# TempControl_V2_0.net
KiCad netlist of a schematic drawn in EAGLE
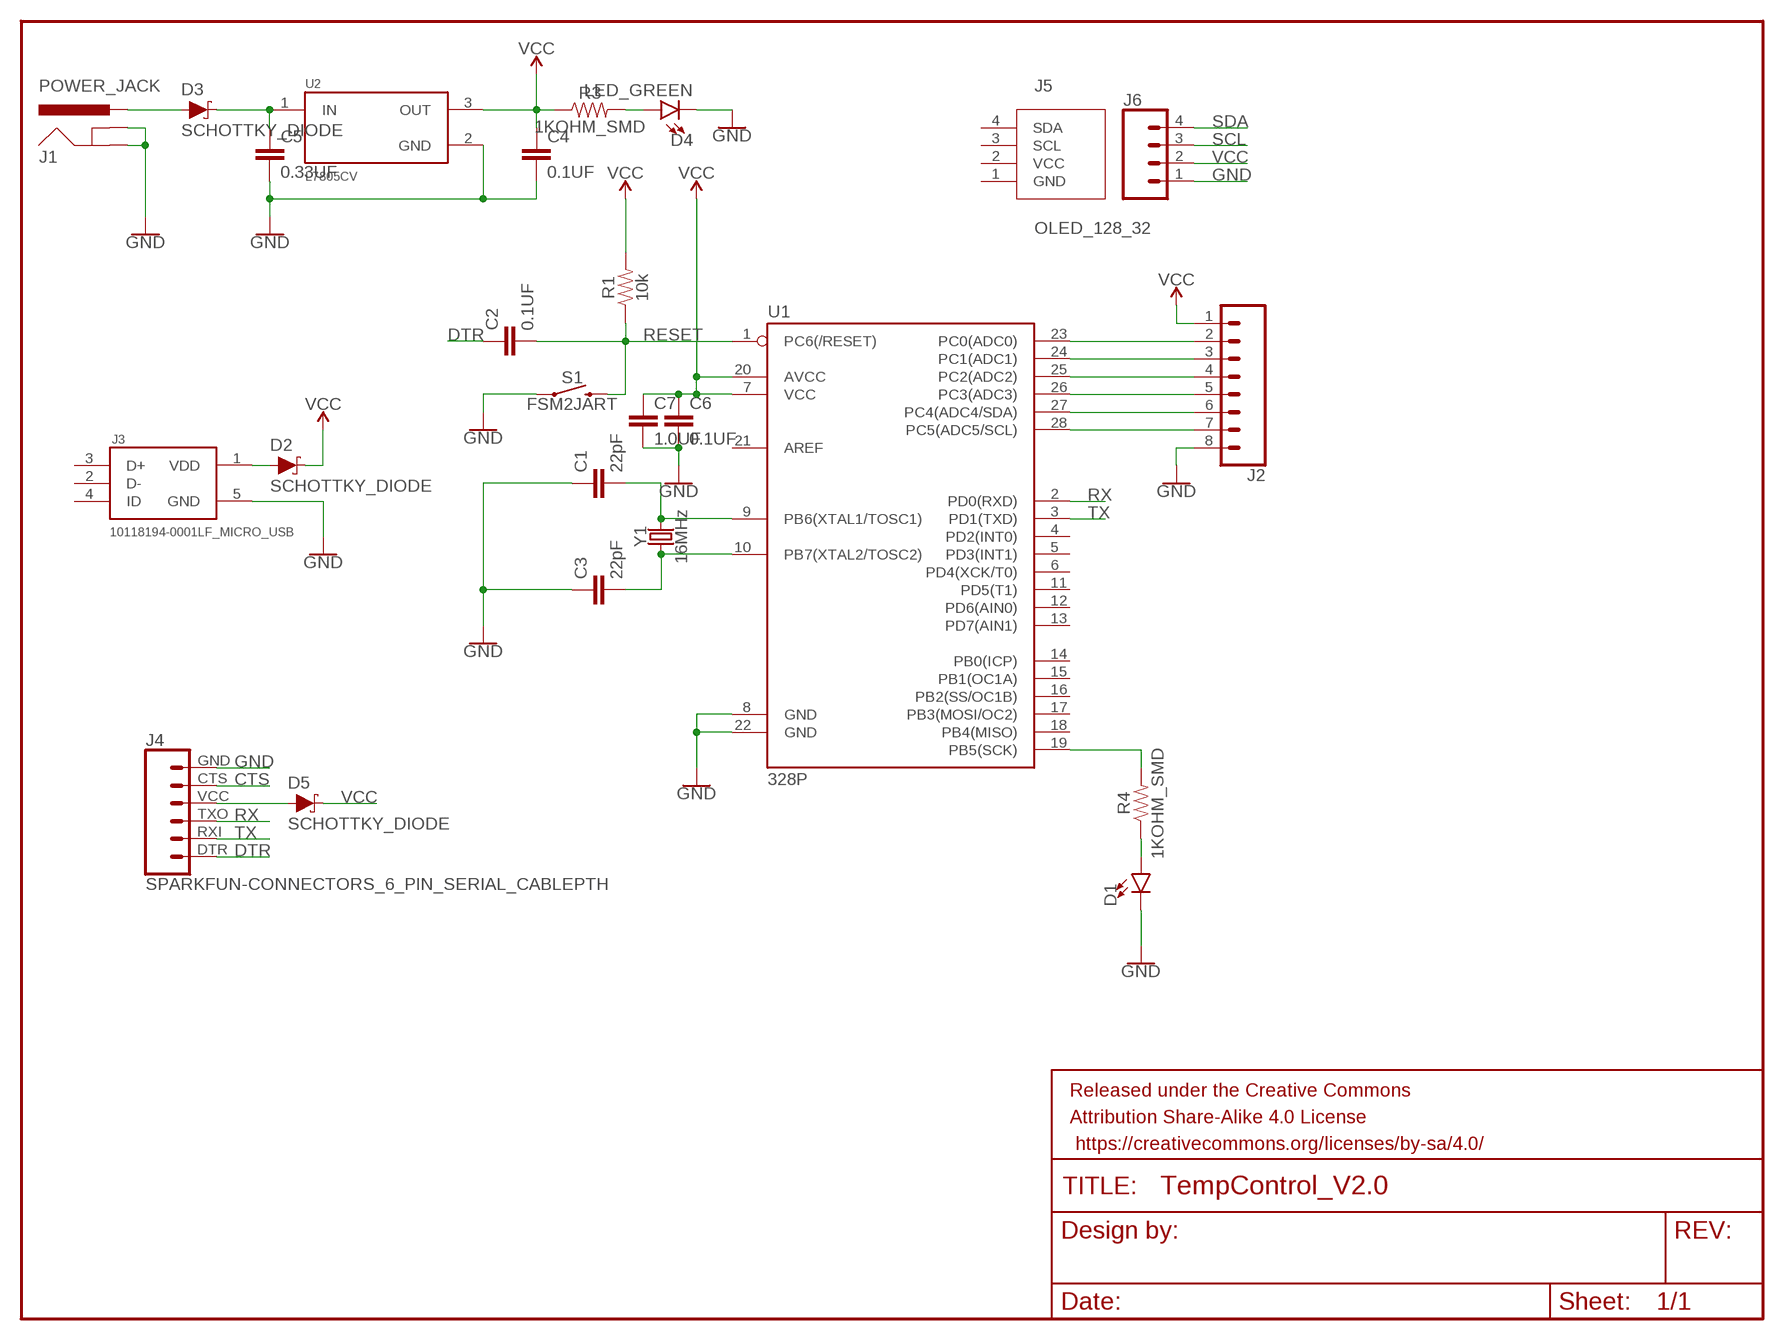
[diagram p0: schematic, sheet 1]

(export (version "E")
  (design (tool "Eeschema 10.0.6"))
  (components
    (comp (ref "C1")
      (value "22pF")
      (footprint "eagle-import:CAP-PTH-2.54")
      (libsource (lib "eagle-import") (part "22PF-PTH-2.54MM-200V-5%"))
    )
    (comp (ref "C2")
      (value "0.1UF")
      (footprint "eagle-import:CAP-PTH-2.54")
      (libsource (lib "eagle-import") (part "0.1UF"))
    )
    (comp (ref "C3")
      (value "22pF")
      (footprint "eagle-import:CAP-PTH-2.54")
      (libsource (lib "eagle-import") (part "22PF-PTH-2.54MM-200V-5%"))
    )
    (comp (ref "C4")
      (value "0.1UF")
      (footprint "eagle-import:CAP-PTH-2.54")
      (libsource (lib "eagle-import") (part "0.1UF"))
    )
    (comp (ref "C5")
      (value "0.33UF")
      (footprint "eagle-import:CAP-PTH-2.54")
      (libsource (lib "eagle-import") (part "0.33UF"))
    )
    (comp (ref "C6")
      (value "0.1UF")
      (footprint "eagle-import:CAP-PTH-2.54")
      (libsource (lib "eagle-import") (part "0.1UF"))
    )
    (comp (ref "C7")
      (value "1.0UF")
      (footprint "eagle-import:CAP-PTH-5MM")
      (libsource (lib "eagle-import") (part "1.0UF"))
    )
    (comp (ref "D1")
      (value "LED_RED5MM")
      (footprint "eagle-import:LED_5MM")
      (libsource (lib "eagle-import") (part "LED_RED5MM"))
    )
    (comp (ref "D2")
      (value "SCHOTTKY_DIODE")
      (footprint "eagle-import:DIODE_0805")
      (libsource (lib "eagle-import") (part "SCHOTTKY_DIODE"))
    )
    (comp (ref "D3")
      (value "SCHOTTKY_DIODE")
      (footprint "eagle-import:DIODE_0805")
      (libsource (lib "eagle-import") (part "SCHOTTKY_DIODE"))
    )
    (comp (ref "D4")
      (value "LED_GREEN")
      (footprint "eagle-import:LED-0603")
      (libsource (lib "eagle-import") (part "LED_GREEN"))
    )
    (comp (ref "D5")
      (value "SCHOTTKY_DIODE")
      (footprint "eagle-import:DIODE_0805")
      (libsource (lib "eagle-import") (part "SCHOTTKY_DIODE"))
    )
    (comp (ref "FRAME1")
      (value "FRAME-LETTERNO_PACKAGE")
      (footprint "eagle-import:DUMMY")
      (fields (field (name "DESIGNER") "Nobody"))
      (libsource (lib "eagle-import") (part "FRAME-LETTERNO_PACKAGE"))
    )
    (comp (ref "J1")
      (value "POWER_JACK")
      (footprint "eagle-import:POWER_JACK_PTH")
      (libsource (lib "eagle-import") (part "POWER_JACK"))
    )
    (comp (ref "J2")
      (value "SPARKFUN-CONNECTORS_CONN_08\"")
      (footprint "eagle-import:SPARKFUN-CONNECTORS_1X08")
      (libsource (lib "eagle-import") (part "SPARKFUN-CONNECTORS_CONN_08{dblquote}"))
    )
    (comp (ref "J3")
      (value "10118194-0001LF_MICRO_USB")
      (footprint "eagle-import:FRAMATOME_10118194-0001LF")
      (fields (field (name "MF") "Amphenol") (field (name "MP") "10118194-0001LF"))
      (libsource (lib "eagle-import") (part "10118194-0001LF_MICRO_USB"))
    )
    (comp (ref "J4")
      (value "SPARKFUN-CONNECTORS_6_PIN_SERIAL_CABLEPTH")
      (footprint "eagle-import:SPARKFUN-CONNECTORS_FTDI_BASIC")
      (libsource (lib "eagle-import") (part "SPARKFUN-CONNECTORS_6_PIN_SERIAL_CABLEPTH"))
    )
    (comp (ref "J5")
      (value "OLED_128_32")
      (footprint "eagle-import:OLED_128_32")
      (libsource (lib "eagle-import") (part "OLED_128_32"))
    )
    (comp (ref "J6")
      (value "CONN_04")
      (footprint "eagle-import:1X04")
      (libsource (lib "eagle-import") (part "CONN_04"))
    )
    (comp (ref "R1")
      (value "10k")
      (footprint "eagle-import:AXIAL-0.3")
      (libsource (lib "eagle-import") (part "10KOHM-HORIZ-1/4W-1%"))
    )
    (comp (ref "R3")
      (value "1KOHM_SMD")
      (footprint "eagle-import:0603")
      (libsource (lib "eagle-import") (part "1KOHM_SMD"))
    )
    (comp (ref "R4")
      (value "1KOHM_SMD")
      (footprint "eagle-import:0603")
      (libsource (lib "eagle-import") (part "1KOHM_SMD"))
    )
    (comp (ref "S1")
      (value "FSM2JART")
      (footprint "eagle-import:FSM2JART")
      (libsource (lib "eagle-import") (part "FSM2JART"))
    )
    (comp (ref "U1")
      (value "328P")
      (footprint "eagle-import:DIP28")
      (libsource (lib "eagle-import") (part "ATMEGA328P_PDIP"))
    )
    (comp (ref "U2")
      (value "L7805CV")
      (footprint "eagle-import:TO254P460X1020X1945-3P")
      (fields (field (name "MF") "STMicroelectronics"))
      (libsource (lib "eagle-import") (part "L7805CV"))
    )
    (comp (ref "Y1")
      (value "16MHz")
      (footprint "eagle-import:HC49US")
      (libsource (lib "eagle-import") (part "CRYSTAL-16MHZPTH-HC49US"))
    )
  )
  (nets
    (net (code "1") (name "/CTS") (class "Default")
      (node (ref "J4") (pin "CTS") (pinfunction "5_CTS") (pintype "passive"))
    )
    (net (code "2") (name "/DTR") (class "Default")
      (node (ref "C2") (pin "1") (pinfunction "1_1") (pintype "passive"))
      (node (ref "J4") (pin "DTR") (pinfunction "1_DTR") (pintype "passive"))
    )
    (net (code "3") (name "/RESET") (class "Default")
      (node (ref "C2") (pin "2") (pinfunction "2_2") (pintype "passive"))
      (node (ref "R1") (pin "P$1") (pinfunction "1_P$1") (pintype "passive"))
      (node (ref "S1") (pin "2") (pinfunction "2_2") (pintype "passive"))
      (node (ref "U1") (pin "1") (pinfunction "PC6(/RESET)_1") (pintype "bidirectional"))
    )
    (net (code "4") (name "/RX") (class "Default")
      (node (ref "J4") (pin "TXO") (pinfunction "3_TXO") (pintype "passive"))
      (node (ref "U1") (pin "2") (pinfunction "PD0(RXD)_2") (pintype "bidirectional"))
    )
    (net (code "5") (name "/SCL") (class "Default")
      (node (ref "J6") (pin "3") (pinfunction "3_3") (pintype "passive"))
    )
    (net (code "6") (name "/SDA") (class "Default")
      (node (ref "J6") (pin "4") (pinfunction "4_4") (pintype "passive"))
    )
    (net (code "7") (name "/TX") (class "Default")
      (node (ref "J4") (pin "RXI") (pinfunction "2_RXI") (pintype "passive"))
      (node (ref "U1") (pin "3") (pinfunction "PD1(TXD)_3") (pintype "bidirectional"))
    )
    (net (code "8") (name "GND") (class "Default")
      (node (ref "C1") (pin "1") (pinfunction "1_1") (pintype "passive"))
      (node (ref "C3") (pin "1") (pinfunction "1_1") (pintype "passive"))
      (node (ref "C4") (pin "2") (pinfunction "2_2") (pintype "passive"))
      (node (ref "C5") (pin "2") (pinfunction "2_2") (pintype "passive"))
      (node (ref "C6") (pin "2") (pinfunction "2_2") (pintype "passive"))
      (node (ref "C7") (pin "2") (pinfunction "2_2") (pintype "passive"))
      (node (ref "D1") (pin "K") (pinfunction "2_K") (pintype "passive"))
      (node (ref "D4") (pin "2") (pinfunction "2_2") (pintype "passive"))
      (node (ref "J1") (pin "GND") (pinfunction "GND_GND") (pintype "bidirectional"))
      (node (ref "J1") (pin "GNDBREAK") (pinfunction "GNDBREAK_GNDBREAK") (pintype "bidirectional"))
      (node (ref "J2") (pin "8") (pinfunction "8_8") (pintype "passive"))
      (node (ref "J3") (pin "5") (pinfunction "GND_5") (pintype "power_in"))
      (node (ref "J4") (pin "GND") (pinfunction "6_GND") (pintype "passive"))
      (node (ref "J6") (pin "1") (pinfunction "1_1") (pintype "passive"))
      (node (ref "S1") (pin "1") (pinfunction "1_1") (pintype "passive"))
      (node (ref "U1") (pin "22") (pinfunction "GND_22") (pintype "bidirectional"))
      (node (ref "U1") (pin "8") (pinfunction "GND_8") (pintype "bidirectional"))
      (node (ref "U2") (pin "2") (pinfunction "GND_2") (pintype "power_in"))
    )
    (net (code "9") (name "Net-(D1-1)") (class "Default")
      (node (ref "D1") (pin "A") (pinfunction "1_A") (pintype "passive"))
      (node (ref "R4") (pin "1") (pinfunction "1_1") (pintype "passive"))
    )
    (net (code "10") (name "Net-(D3-Pad1)") (class "Default")
      (node (ref "D3") (pin "1") (pinfunction "1_1") (pintype "passive"))
      (node (ref "J1") (pin "PWR") (pinfunction "PWR_PWR") (pintype "bidirectional"))
    )
    (net (code "11") (name "Net-(D4-Pad1)") (class "Default")
      (node (ref "D4") (pin "1") (pinfunction "1_1") (pintype "passive"))
      (node (ref "R3") (pin "2") (pinfunction "2_2") (pintype "passive"))
    )
    (net (code "12") (name "Net-(J3-VDD)") (class "Default")
      (node (ref "D2") (pin "1") (pinfunction "1_1") (pintype "passive"))
      (node (ref "J3") (pin "1") (pinfunction "VDD_1") (pintype "power_in"))
    )
    (net (code "13") (name "Net-(J4-4)") (class "Default")
      (node (ref "D5") (pin "1") (pinfunction "1_1") (pintype "passive"))
      (node (ref "J4") (pin "VCC") (pinfunction "4_VCC") (pintype "passive"))
    )
    (net (code "14") (name "Net-(U1-PB5(SCK))") (class "Default")
      (node (ref "R4") (pin "2") (pinfunction "2_2") (pintype "passive"))
      (node (ref "U1") (pin "19") (pinfunction "PB5(SCK)_19") (pintype "bidirectional"))
    )
    (net (code "15") (name "Net-(U1-PB6(XTAL1{slash}TOSC1))") (class "Default")
      (node (ref "C1") (pin "2") (pinfunction "2_2") (pintype "passive"))
      (node (ref "U1") (pin "9") (pinfunction "PB6(XTAL1/TOSC1)_9") (pintype "bidirectional"))
      (node (ref "Y1") (pin "2") (pinfunction "2_2") (pintype "passive"))
    )
    (net (code "16") (name "Net-(U1-PB7(XTAL2{slash}TOSC2))") (class "Default")
      (node (ref "C3") (pin "2") (pinfunction "2_2") (pintype "passive"))
      (node (ref "U1") (pin "10") (pinfunction "PB7(XTAL2/TOSC2)_10") (pintype "bidirectional"))
      (node (ref "Y1") (pin "1") (pinfunction "1_1") (pintype "passive"))
    )
    (net (code "17") (name "Net-(U1-PC0(ADC0))") (class "Default")
      (node (ref "J2") (pin "2") (pinfunction "2_2") (pintype "passive"))
      (node (ref "U1") (pin "23") (pinfunction "PC0(ADC0)_23") (pintype "bidirectional"))
    )
    (net (code "18") (name "Net-(U1-PC1(ADC1))") (class "Default")
      (node (ref "J2") (pin "3") (pinfunction "3_3") (pintype "passive"))
      (node (ref "U1") (pin "24") (pinfunction "PC1(ADC1)_24") (pintype "bidirectional"))
    )
    (net (code "19") (name "Net-(U1-PC2(ADC2))") (class "Default")
      (node (ref "J2") (pin "4") (pinfunction "4_4") (pintype "passive"))
      (node (ref "U1") (pin "25") (pinfunction "PC2(ADC2)_25") (pintype "bidirectional"))
    )
    (net (code "20") (name "Net-(U1-PC3(ADC3))") (class "Default")
      (node (ref "J2") (pin "5") (pinfunction "5_5") (pintype "passive"))
      (node (ref "U1") (pin "26") (pinfunction "PC3(ADC3)_26") (pintype "bidirectional"))
    )
    (net (code "21") (name "Net-(U1-PC4(ADC4{slash}SDA))") (class "Default")
      (node (ref "J2") (pin "6") (pinfunction "6_6") (pintype "passive"))
      (node (ref "U1") (pin "27") (pinfunction "PC4(ADC4/SDA)_27") (pintype "bidirectional"))
    )
    (net (code "22") (name "Net-(U1-PC5(ADC5{slash}SCL))") (class "Default")
      (node (ref "J2") (pin "7") (pinfunction "7_7") (pintype "passive"))
      (node (ref "U1") (pin "28") (pinfunction "PC5(ADC5/SCL)_28") (pintype "bidirectional"))
    )
    (net (code "23") (name "Net-(U2-IN)") (class "Default")
      (node (ref "C5") (pin "1") (pinfunction "1_1") (pintype "passive"))
      (node (ref "D3") (pin "2") (pinfunction "2_2") (pintype "passive"))
      (node (ref "U2") (pin "1") (pinfunction "IN_1") (pintype "input"))
    )
    (net (code "24") (name "VCC") (class "Default")
      (node (ref "C4") (pin "1") (pinfunction "1_1") (pintype "passive"))
      (node (ref "C6") (pin "1") (pinfunction "1_1") (pintype "passive"))
      (node (ref "C7") (pin "1") (pinfunction "1_1") (pintype "passive"))
      (node (ref "D2") (pin "2") (pinfunction "2_2") (pintype "passive"))
      (node (ref "D5") (pin "2") (pinfunction "2_2") (pintype "passive"))
      (node (ref "J2") (pin "1") (pinfunction "1_1") (pintype "passive"))
      (node (ref "J6") (pin "2") (pinfunction "2_2") (pintype "passive"))
      (node (ref "R1") (pin "P$2") (pinfunction "2_P$2") (pintype "passive"))
      (node (ref "R3") (pin "1") (pinfunction "1_1") (pintype "passive"))
      (node (ref "U1") (pin "20") (pinfunction "AVCC_20") (pintype "bidirectional"))
      (node (ref "U1") (pin "7") (pinfunction "VCC_7") (pintype "bidirectional"))
      (node (ref "U2") (pin "3") (pinfunction "OUT_3") (pintype "power_in"))
    )
    (net (code "25") (name "unconnected-(J3-D+-Pad3)") (class "Default")
      (node (ref "J3") (pin "3") (pinfunction "D+_3") (pintype "bidirectional"))
    )
    (net (code "26") (name "unconnected-(J3-D--Pad2)") (class "Default")
      (node (ref "J3") (pin "2") (pinfunction "D-_2") (pintype "bidirectional"))
    )
    (net (code "27") (name "unconnected-(J3-ID-Pad4)") (class "Default")
      (node (ref "J3") (pin "4") (pinfunction "ID_4") (pintype "passive"))
    )
    (net (code "28") (name "unconnected-(J5-GND-Pad1)") (class "Default")
      (node (ref "J5") (pin "1") (pinfunction "GND_1") (pintype "bidirectional"))
    )
    (net (code "29") (name "unconnected-(J5-SCL-Pad3)") (class "Default")
      (node (ref "J5") (pin "3") (pinfunction "SCL_3") (pintype "bidirectional"))
    )
    (net (code "30") (name "unconnected-(J5-SDA-Pad4)") (class "Default")
      (node (ref "J5") (pin "4") (pinfunction "SDA_4") (pintype "bidirectional"))
    )
    (net (code "31") (name "unconnected-(J5-VCC-Pad2)") (class "Default")
      (node (ref "J5") (pin "2") (pinfunction "VCC_2") (pintype "bidirectional"))
    )
    (net (code "32") (name "unconnected-(U1-AREF-Pad21)") (class "Default")
      (node (ref "U1") (pin "21") (pinfunction "AREF_21") (pintype "bidirectional"))
    )
    (net (code "33") (name "unconnected-(U1-PB0(ICP)-Pad14)") (class "Default")
      (node (ref "U1") (pin "14") (pinfunction "PB0(ICP)_14") (pintype "bidirectional"))
    )
    (net (code "34") (name "unconnected-(U1-PB1(OC1A)-Pad15)") (class "Default")
      (node (ref "U1") (pin "15") (pinfunction "PB1(OC1A)_15") (pintype "bidirectional"))
    )
    (net (code "35") (name "unconnected-(U1-PB2(SS{slash}OC1B)-Pad16)") (class "Default")
      (node (ref "U1") (pin "16") (pinfunction "PB2(SS/OC1B)_16") (pintype "bidirectional"))
    )
    (net (code "36") (name "unconnected-(U1-PB3(MOSI{slash}OC2)-Pad17)") (class "Default")
      (node (ref "U1") (pin "17") (pinfunction "PB3(MOSI/OC2)_17") (pintype "bidirectional"))
    )
    (net (code "37") (name "unconnected-(U1-PB4(MISO)-Pad18)") (class "Default")
      (node (ref "U1") (pin "18") (pinfunction "PB4(MISO)_18") (pintype "bidirectional"))
    )
    (net (code "38") (name "unconnected-(U1-PD2(INT0)-Pad4)") (class "Default")
      (node (ref "U1") (pin "4") (pinfunction "PD2(INT0)_4") (pintype "bidirectional"))
    )
    (net (code "39") (name "unconnected-(U1-PD3(INT1)-Pad5)") (class "Default")
      (node (ref "U1") (pin "5") (pinfunction "PD3(INT1)_5") (pintype "bidirectional"))
    )
    (net (code "40") (name "unconnected-(U1-PD4(XCK{slash}T0)-Pad6)") (class "Default")
      (node (ref "U1") (pin "6") (pinfunction "PD4(XCK/T0)_6") (pintype "bidirectional"))
    )
    (net (code "41") (name "unconnected-(U1-PD5(T1)-Pad11)") (class "Default")
      (node (ref "U1") (pin "11") (pinfunction "PD5(T1)_11") (pintype "bidirectional"))
    )
    (net (code "42") (name "unconnected-(U1-PD6(AIN0)-Pad12)") (class "Default")
      (node (ref "U1") (pin "12") (pinfunction "PD6(AIN0)_12") (pintype "bidirectional"))
    )
    (net (code "43") (name "unconnected-(U1-PD7(AIN1)-Pad13)") (class "Default")
      (node (ref "U1") (pin "13") (pinfunction "PD7(AIN1)_13") (pintype "bidirectional"))
    )
  )
)
